# DMB.net
KiCad netlist of a schematic drawn in Altium Designer
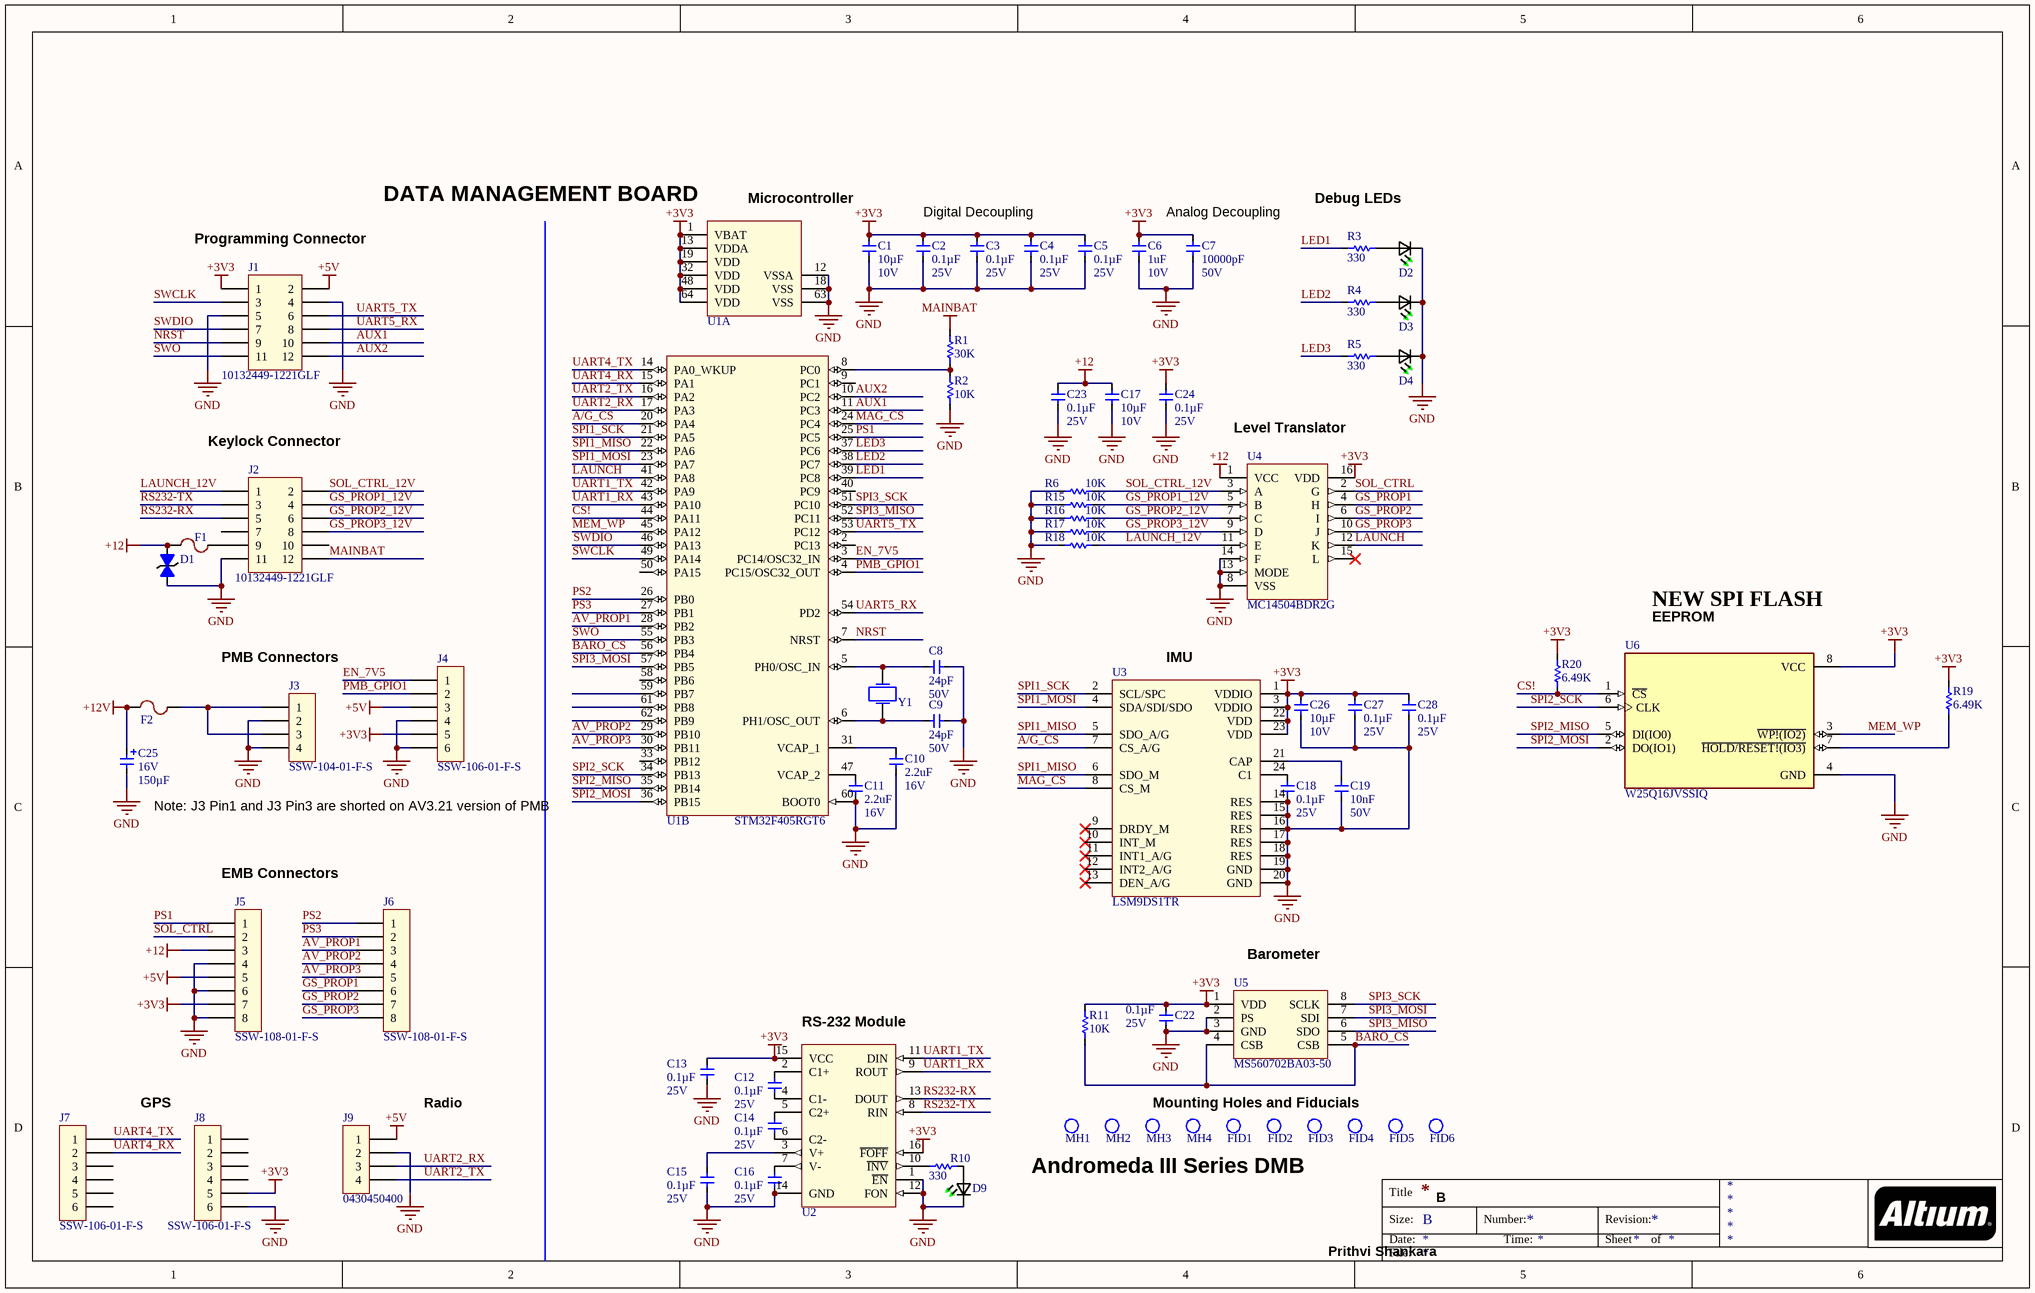
[diagram p0: DMB.SchDoc]

(export (version "E")
  (design (tool "Eeschema 10.0.6"))
  (components
    (comp (ref "C1")
      (value "CL10A106MP8NNNC")
      (footprint "0603[1608]")
      (description "CAP CER 10UF 10V X5R 0603")
      (fields
        (field (name "MANUFACTURER") "Samsung Electro-Mechanics")
        (field (name "TOLERANCE") "±20%")
        (field (name "CAPACITANCE") "10µF")
        (field (name "VOLTAGE - RATED") "10V")
      )
      (libsource (lib "SOARSchematics") (part "CL10A106MP8NNNC"))
    )
    (comp (ref "C2")
      (value "CGA3E2X7R1E104K080AA")
      (footprint "0603[1608]")
      (description "CAP CER 0.1UF 25V X7R 0603")
      (fields
        (field (name "MANUFACTURER") "TDK Corporation")
        (field (name "TOLERANCE") "±10%")
        (field (name "CAPACITANCE") "0.1µF")
        (field (name "VOLTAGE - RATED") "25V")
      )
      (libsource (lib "SOARSchematics") (part "CGA3E2X7R1E104K080AA"))
    )
    (comp (ref "C3")
      (value "CGA3E2X7R1E104K080AA")
      (footprint "0603[1608]")
      (description "CAP CER 0.1UF 25V X7R 0603")
      (fields
        (field (name "MANUFACTURER") "TDK Corporation")
        (field (name "TOLERANCE") "±10%")
        (field (name "CAPACITANCE") "0.1µF")
        (field (name "VOLTAGE - RATED") "25V")
      )
      (libsource (lib "SOARSchematics") (part "CGA3E2X7R1E104K080AA"))
    )
    (comp (ref "C4")
      (value "CGA3E2X7R1E104K080AA")
      (footprint "0603[1608]")
      (description "CAP CER 0.1UF 25V X7R 0603")
      (fields
        (field (name "MANUFACTURER") "TDK Corporation")
        (field (name "TOLERANCE") "±10%")
        (field (name "CAPACITANCE") "0.1µF")
        (field (name "VOLTAGE - RATED") "25V")
      )
      (libsource (lib "SOARSchematics") (part "CGA3E2X7R1E104K080AA"))
    )
    (comp (ref "C5")
      (value "CGA3E2X7R1E104K080AA")
      (footprint "0603[1608]")
      (description "CAP CER 0.1UF 25V X7R 0603")
      (fields
        (field (name "MANUFACTURER") "TDK Corporation")
        (field (name "TOLERANCE") "±10%")
        (field (name "CAPACITANCE") "0.1µF")
        (field (name "VOLTAGE - RATED") "25V")
      )
      (libsource (lib "SOARSchematics") (part "CGA3E2X7R1E104K080AA"))
    )
    (comp (ref "C6")
      (value "CL10A105KP8NNNC")
      (footprint "0603[1608]")
      (description "CAP CER 1UF 10V X5R 0603")
      (fields
        (field (name "MANUFACTURER") "Samsung Electro-Mechanics")
        (field (name "TOLERANCE") "±10%")
        (field (name "CAPACITANCE") "1uF")
        (field (name "VOLTAGE - RATED") "10V")
      )
      (libsource (lib "SOARSchematics") (part "CL10A105KP8NNNC"))
    )
    (comp (ref "C7")
      (value "CGA3E2X7R1H103K080AA")
      (footprint "0603[1608]")
      (description "CAP CER 10000PF 50V X7R 0603")
      (fields
        (field (name "MANUFACTURER") "TDK Corporation")
        (field (name "TOLERANCE") "±10%")
        (field (name "CAPACITANCE") "10000pF")
        (field (name "VOLTAGE - RATED") "50V")
      )
      (libsource (lib "SOARSchematics") (part "CGA3E2X7R1H103K080AA"))
    )
    (comp (ref "C8")
      (value "06035A240JAT2A")
      (footprint "0603[1608]")
      (description "CAP CER 24PF 50V NP0 0603")
      (fields
        (field (name "MANUFACTURER") "AVX Corporation")
        (field (name "TOLERANCE") "±5%")
        (field (name "CAPACITANCE") "24pF")
        (field (name "VOLTAGE - RATED") "50V")
      )
      (libsource (lib "SOARSchematics") (part "06035A240JAT2A"))
    )
    (comp (ref "C9")
      (value "06035A240JAT2A")
      (footprint "0603[1608]")
      (description "CAP CER 24PF 50V NP0 0603")
      (fields
        (field (name "MANUFACTURER") "AVX Corporation")
        (field (name "TOLERANCE") "±5%")
        (field (name "CAPACITANCE") "24pF")
        (field (name "VOLTAGE - RATED") "50V")
      )
      (libsource (lib "SOARSchematics") (part "06035A240JAT2A"))
    )
    (comp (ref "C10")
      (value "C1608X5R1C225K080AB")
      (footprint "0603[1608]")
      (description "CAP CER 2.2UF 16V X5R 0603")
      (fields
        (field (name "MANUFACTURER") "TDK Corporation")
        (field (name "TOLERANCE") "±10%")
        (field (name "CAPACITANCE") "2.2uF")
        (field (name "VOLTAGE - RATED") "16V")
      )
      (libsource (lib "SOARSchematics") (part "C1608X5R1C225K080AB"))
    )
    (comp (ref "C11")
      (value "C1608X5R1C225K080AB")
      (footprint "0603[1608]")
      (description "CAP CER 2.2UF 16V X5R 0603")
      (fields
        (field (name "MANUFACTURER") "TDK Corporation")
        (field (name "TOLERANCE") "±10%")
        (field (name "CAPACITANCE") "2.2uF")
        (field (name "VOLTAGE - RATED") "16V")
      )
      (libsource (lib "SOARSchematics") (part "C1608X5R1C225K080AB"))
    )
    (comp (ref "C12")
      (value "CGA3E2X7R1E104K080AA")
      (footprint "0603[1608]")
      (description "CAP CER 0.1UF 25V X7R 0603")
      (fields
        (field (name "MANUFACTURER") "TDK Corporation")
        (field (name "TOLERANCE") "±10%")
        (field (name "CAPACITANCE") "0.1µF")
        (field (name "VOLTAGE - RATED") "25V")
      )
      (libsource (lib "SOARSchematics") (part "CGA3E2X7R1E104K080AA"))
    )
    (comp (ref "C13")
      (value "CGA3E2X7R1E104K080AA")
      (footprint "0603[1608]")
      (description "CAP CER 0.1UF 25V X7R 0603")
      (fields
        (field (name "MANUFACTURER") "TDK Corporation")
        (field (name "TOLERANCE") "±10%")
        (field (name "CAPACITANCE") "0.1µF")
        (field (name "VOLTAGE - RATED") "25V")
      )
      (libsource (lib "SOARSchematics") (part "CGA3E2X7R1E104K080AA"))
    )
    (comp (ref "C14")
      (value "CGA3E2X7R1E104K080AA")
      (footprint "0603[1608]")
      (description "CAP CER 0.1UF 25V X7R 0603")
      (fields
        (field (name "MANUFACTURER") "TDK Corporation")
        (field (name "TOLERANCE") "±10%")
        (field (name "CAPACITANCE") "0.1µF")
        (field (name "VOLTAGE - RATED") "25V")
      )
      (libsource (lib "SOARSchematics") (part "CGA3E2X7R1E104K080AA"))
    )
    (comp (ref "C15")
      (value "CGA3E2X7R1E104K080AA")
      (footprint "0603[1608]")
      (description "CAP CER 0.1UF 25V X7R 0603")
      (fields
        (field (name "MANUFACTURER") "TDK Corporation")
        (field (name "TOLERANCE") "±10%")
        (field (name "CAPACITANCE") "0.1µF")
        (field (name "VOLTAGE - RATED") "25V")
      )
      (libsource (lib "SOARSchematics") (part "CGA3E2X7R1E104K080AA"))
    )
    (comp (ref "C16")
      (value "CGA3E2X7R1E104K080AA")
      (footprint "0603[1608]")
      (description "CAP CER 0.1UF 25V X7R 0603")
      (fields
        (field (name "MANUFACTURER") "TDK Corporation")
        (field (name "TOLERANCE") "±10%")
        (field (name "CAPACITANCE") "0.1µF")
        (field (name "VOLTAGE - RATED") "25V")
      )
      (libsource (lib "SOARSchematics") (part "CGA3E2X7R1E104K080AA"))
    )
    (comp (ref "C17")
      (value "CL10A106MP8NNNC")
      (footprint "0603[1608]")
      (description "CAP CER 10UF 10V X5R 0603")
      (fields
        (field (name "MANUFACTURER") "Samsung Electro-Mechanics")
        (field (name "TOLERANCE") "±20%")
        (field (name "CAPACITANCE") "10µF")
        (field (name "VOLTAGE - RATED") "10V")
      )
      (libsource (lib "SOARSchematics") (part "CL10A106MP8NNNC"))
    )
    (comp (ref "C18")
      (value "CGA3E2X7R1E104K080AA")
      (footprint "0603[1608]")
      (description "CAP CER 0.1UF 25V X7R 0603")
      (fields
        (field (name "MANUFACTURER") "TDK Corporation")
        (field (name "TOLERANCE") "±10%")
        (field (name "CAPACITANCE") "0.1µF")
        (field (name "VOLTAGE - RATED") "25V")
      )
      (libsource (lib "SOARSchematics") (part "CGA3E2X7R1E104K080AA"))
    )
    (comp (ref "C19")
      (value "GRM1885C1H103JA01D")
      (footprint "0603[1608]")
      (description "CAP CER 10000PF 50V C0G/NP0 0603")
      (fields
        (field (name "MANUFACTURER") "Murata Electronics")
        (field (name "TOLERANCE") "±50%")
        (field (name "CAPACITANCE") "10nF")
        (field (name "VOLTAGE - RATED") "50V")
      )
      (libsource (lib "SOARSchematics") (part "GRM1885C1H103JA01D"))
    )
    (comp (ref "C22")
      (value "CGA3E2X7R1E104K080AA")
      (footprint "0603[1608]")
      (description "CAP CER 0.1UF 25V X7R 0603")
      (fields
        (field (name "MANUFACTURER") "TDK Corporation")
        (field (name "TOLERANCE") "±10%")
        (field (name "CAPACITANCE") "0.1µF")
        (field (name "VOLTAGE - RATED") "25V")
      )
      (libsource (lib "SOARSchematics") (part "CGA3E2X7R1E104K080AA"))
    )
    (comp (ref "C23")
      (value "CGA3E2X7R1E104K080AA")
      (footprint "0603[1608]")
      (description "CAP CER 0.1UF 25V X7R 0603")
      (fields
        (field (name "MANUFACTURER") "TDK Corporation")
        (field (name "TOLERANCE") "±10%")
        (field (name "CAPACITANCE") "0.1µF")
        (field (name "VOLTAGE - RATED") "25V")
      )
      (libsource (lib "SOARSchematics") (part "CGA3E2X7R1E104K080AA"))
    )
    (comp (ref "C24")
      (value "CGA3E2X7R1E104K080AA")
      (footprint "0603[1608]")
      (description "CAP CER 0.1UF 25V X7R 0603")
      (fields
        (field (name "MANUFACTURER") "TDK Corporation")
        (field (name "TOLERANCE") "±10%")
        (field (name "CAPACITANCE") "0.1µF")
        (field (name "VOLTAGE - RATED") "25V")
      )
      (libsource (lib "SOARSchematics") (part "CGA3E2X7R1E104K080AA"))
    )
    (comp (ref "C25")
      (value "TAJD157K016RNJ")
      (footprint "TAJD157K016RNJ")
      (description "CAP TANT 150UF 10% 16V 2917")
      (fields
        (field (name "MANUFACTURER") "AVX Corporation")
        (field (name "TOLERANCE") "±10%")
        (field (name "VOLTAGE - RATED") "16V")
        (field (name "CAPACITANCE") "150µF")
      )
      (libsource (lib "SOARSchematics") (part "TAJD157K016RNJ"))
    )
    (comp (ref "C26")
      (value "CL10A106MP8NNNC")
      (footprint "0603[1608]")
      (description "CAP CER 10UF 10V X5R 0603")
      (fields
        (field (name "MANUFACTURER") "Samsung Electro-Mechanics")
        (field (name "TOLERANCE") "±20%")
        (field (name "CAPACITANCE") "10µF")
        (field (name "VOLTAGE - RATED") "10V")
      )
      (libsource (lib "SOARSchematics") (part "CL10A106MP8NNNC"))
    )
    (comp (ref "C27")
      (value "CGA3E2X7R1E104K080AA")
      (footprint "0603[1608]")
      (description "CAP CER 0.1UF 25V X7R 0603")
      (fields
        (field (name "MANUFACTURER") "TDK Corporation")
        (field (name "TOLERANCE") "±10%")
        (field (name "CAPACITANCE") "0.1µF")
        (field (name "VOLTAGE - RATED") "25V")
      )
      (libsource (lib "SOARSchematics") (part "CGA3E2X7R1E104K080AA"))
    )
    (comp (ref "C28")
      (value "CGA3E2X7R1E104K080AA")
      (footprint "0603[1608]")
      (description "CAP CER 0.1UF 25V X7R 0603")
      (fields
        (field (name "MANUFACTURER") "TDK Corporation")
        (field (name "TOLERANCE") "±10%")
        (field (name "CAPACITANCE") "0.1µF")
        (field (name "VOLTAGE - RATED") "25V")
      )
      (libsource (lib "SOARSchematics") (part "CGA3E2X7R1E104K080AA"))
    )
    (comp (ref "D1")
      (value "CDSOD323-T12C")
      (footprint "CDSOD323-T12C")
      (description "TVS DIODE 12V 28.3V SOD323")
      (fields (field (name "MANUFACTURER") "Bourns Inc."))
      (libsource (lib "SOARSchematics") (part "CDSOD323-T12C"))
    )
    (comp (ref "D2")
      (value "LTST-C191KGKT")
      (footprint "LTST-C191KGKT")
      (description "LED GREEN CLEAR SMD 0603")
      (fields (field (name "MANUFACTURER") "Lite-On Inc."))
      (libsource (lib "SOARSchematics") (part "LTST-C191KGKT"))
    )
    (comp (ref "D3")
      (value "LTST-C191KGKT")
      (footprint "LTST-C191KGKT")
      (description "LED GREEN CLEAR SMD 0603")
      (fields (field (name "MANUFACTURER") "Lite-On Inc."))
      (libsource (lib "SOARSchematics") (part "LTST-C191KGKT"))
    )
    (comp (ref "D4")
      (value "LTST-C191KGKT")
      (footprint "LTST-C191KGKT")
      (description "LED GREEN CLEAR SMD 0603")
      (fields (field (name "MANUFACTURER") "Lite-On Inc."))
      (libsource (lib "SOARSchematics") (part "LTST-C191KGKT"))
    )
    (comp (ref "D9")
      (value "LTST-C191KGKT")
      (footprint "LTST-C191KGKT")
      (description "LED GREEN CLEAR SMD 0603")
      (fields (field (name "MANUFACTURER") "Lite-On Inc."))
      (libsource (lib "SOARSchematics") (part "LTST-C191KGKT"))
    )
    (comp (ref "F1")
      (value "SF-0603FP500M-2")
      (footprint "SF-0603FP500M-2")
      (description "FUSE BOARD MOUNT 5A 32VDC 0603")
      (fields (field (name "MANUFACTURER") "Bourns Inc."))
      (libsource (lib "SOARSchematics") (part "SF-0603FP500M-2"))
    )
    (comp (ref "F2")
      (value "SF-0603FP500M-2")
      (footprint "SF-0603FP500M-2")
      (description "FUSE BOARD MOUNT 5A 32VDC 0603")
      (fields (field (name "MANUFACTURER") "Bourns Inc."))
      (libsource (lib "SOARSchematics") (part "SF-0603FP500M-2"))
    )
    (comp (ref "FID1")
      (value "FID_1MM_ROUND_SL")
      (footprint "FID_1MM_ROUND_SL")
      (description "Fiducial 1mm Round Single Layer")
      (libsource (lib "SOARSchematics") (part "FID_1MM_ROUND_SL"))
    )
    (comp (ref "FID2")
      (value "FID_1MM_ROUND_SL")
      (footprint "FID_1MM_ROUND_SL")
      (description "Fiducial 1mm Round Single Layer")
      (libsource (lib "SOARSchematics") (part "FID_1MM_ROUND_SL"))
    )
    (comp (ref "FID3")
      (value "FID_1MM_ROUND_SL")
      (footprint "FID_1MM_ROUND_SL")
      (description "Fiducial 1mm Round Single Layer")
      (libsource (lib "SOARSchematics") (part "FID_1MM_ROUND_SL"))
    )
    (comp (ref "FID4")
      (value "FID_1MM_ROUND_SL")
      (footprint "FID_1MM_ROUND_SL")
      (description "Fiducial 1mm Round Single Layer")
      (libsource (lib "SOARSchematics") (part "FID_1MM_ROUND_SL"))
    )
    (comp (ref "FID5")
      (value "FID_1MM_ROUND_SL")
      (footprint "FID_1MM_ROUND_SL")
      (description "Fiducial 1mm Round Single Layer")
      (libsource (lib "SOARSchematics") (part "FID_1MM_ROUND_SL"))
    )
    (comp (ref "FID6")
      (value "FID_1MM_ROUND_SL")
      (footprint "FID_1MM_ROUND_SL")
      (description "Fiducial 1mm Round Single Layer")
      (libsource (lib "SOARSchematics") (part "FID_1MM_ROUND_SL"))
    )
    (comp (ref "J1")
      (value "10132449-1221GLF")
      (footprint "10132449-1221GLF")
      (description "CONN HEADER R/A 12POS 3MM")
      (fields (field (name "MANUFACTURER") "Amphenol ICC (FCI)"))
      (libsource (lib "SOARSchematics") (part "10132449-1221GLF"))
    )
    (comp (ref "J2")
      (value "10132449-1221GLF")
      (footprint "10132449-1221GLF")
      (description "CONN HEADER R/A 12POS 3MM")
      (fields (field (name "MANUFACTURER") "Amphenol ICC (FCI)"))
      (libsource (lib "SOARSchematics") (part "10132449-1221GLF"))
    )
    (comp (ref "J3")
      (value "SSW-104-01-F-S")
      (footprint "SSW-104-01-F-S")
      (description "CONN RCPT 4POS FEMALE 0.1 GOLD PCB")
      (fields (field (name "MANUFACTURER") "Samtec Inc."))
      (libsource (lib "SOARSchematics") (part "SSW-104-01-F-S"))
    )
    (comp (ref "J4")
      (value "SSW-106-01-F-S")
      (footprint "SSW-106-01-F-S")
      (description "CONN RCPT 6POS FEMALE 0.1 GOLD PCB")
      (fields (field (name "MANUFACTURER") "Samtec Inc."))
      (libsource (lib "") (part "SSW-106-01-F-S_1"))
    )
    (comp (ref "J5")
      (value "SSW-108-01-F-S")
      (footprint "SSW-108-01-F-S")
      (description "CONN RCPT 8POS FEMALE 0.1 GOLD PCB")
      (fields (field (name "MANUFACTURER") "Samtec Inc."))
      (libsource (lib "SOARSchematics") (part "SSW-108-01-F-S"))
    )
    (comp (ref "J6")
      (value "SSW-108-01-F-S")
      (footprint "SSW-108-01-F-S")
      (description "CONN RCPT 8POS FEMALE 0.1 GOLD PCB")
      (fields (field (name "MANUFACTURER") "Samtec Inc."))
      (libsource (lib "SOARSchematics") (part "SSW-108-01-F-S"))
    )
    (comp (ref "J7")
      (value "SSW-106-01-F-S")
      (footprint "SSW-106-01-F-S")
      (description "CONN RCPT 6POS FEMALE 0.1 GOLD PCB")
      (fields (field (name "MANUFACTURER") "Samtec Inc."))
      (libsource (lib "SOARSchematics") (part "SSW-106-01-F-S"))
    )
    (comp (ref "J8")
      (value "SSW-106-01-F-S")
      (footprint "SSW-106-01-F-S")
      (description "CONN RCPT 6POS FEMALE 0.1 GOLD PCB")
      (fields (field (name "MANUFACTURER") "Samtec Inc."))
      (libsource (lib "SOARSchematics") (part "SSW-106-01-F-S"))
    )
    (comp (ref "J9")
      (value "0430450400")
      (footprint "0430450400")
      (description "CONN HEADER R/A 4POS 3MM")
      (fields (field (name "MANUFACTURER") "Molex"))
      (libsource (lib "SOARSchematics") (part "0430450400"))
    )
    (comp (ref "MH1")
      (value "Mounting Hole")
      (footprint "MOUNT-HOLE")
      (description "#4 Screw, 0.116in Diameter")
      (libsource (lib "SOARSchematics") (part "Mounting Hole"))
    )
    (comp (ref "MH2")
      (value "Mounting Hole")
      (footprint "MOUNT-HOLE")
      (description "#4 Screw, 0.116in Diameter")
      (libsource (lib "SOARSchematics") (part "Mounting Hole"))
    )
    (comp (ref "MH3")
      (value "Mounting Hole")
      (footprint "MOUNT-HOLE")
      (description "#4 Screw, 0.116in Diameter")
      (libsource (lib "SOARSchematics") (part "Mounting Hole"))
    )
    (comp (ref "MH4")
      (value "Mounting Hole")
      (footprint "MOUNT-HOLE")
      (description "#4 Screw, 0.116in Diameter")
      (libsource (lib "SOARSchematics") (part "Mounting Hole"))
    )
    (comp (ref "R1")
      (value "RC0603FR-0730KL")
      (footprint "0603[1608]")
      (description "RES SMD 30K OHM 1% 1/10W 0603")
      (fields
        (field (name "TOLERANCE") "±1%")
        (field (name "MANUFACTURER") "Yageo")
        (field (name "RESISTANCE") "30K")
      )
      (libsource (lib "SOARSchematics") (part "RC0603FR-0730KL"))
    )
    (comp (ref "R2")
      (value "ERJ-3GEYJ103V")
      (footprint "0603[1608]")
      (description "RES SMD 10K OHM 5% 1/10W 0603")
      (fields
        (field (name "TOLERANCE") "±5%")
        (field (name "MANUFACTURER") "Panasonic Electronic Components")
        (field (name "RESISTANCE") "10K")
      )
      (libsource (lib "SOARSchematics") (part "ERJ-3GEYJ103V"))
    )
    (comp (ref "R3")
      (value "RC1608F331CS")
      (footprint "0603[1608]")
      (description "RES SMD 330 OHM 1% 1/10W 0603")
      (fields
        (field (name "TOLERANCE") "±1%")
        (field (name "MANUFACTURER") "Samsung Electro-Mechanics")
        (field (name "RESISTANCE") "330")
      )
      (libsource (lib "SOARSchematics") (part "RC1608F331CS"))
    )
    (comp (ref "R4")
      (value "RC1608F331CS")
      (footprint "0603[1608]")
      (description "RES SMD 330 OHM 1% 1/10W 0603")
      (fields
        (field (name "TOLERANCE") "±1%")
        (field (name "MANUFACTURER") "Samsung Electro-Mechanics")
        (field (name "RESISTANCE") "330")
      )
      (libsource (lib "SOARSchematics") (part "RC1608F331CS"))
    )
    (comp (ref "R5")
      (value "RC1608F331CS")
      (footprint "0603[1608]")
      (description "RES SMD 330 OHM 1% 1/10W 0603")
      (fields
        (field (name "TOLERANCE") "±1%")
        (field (name "MANUFACTURER") "Samsung Electro-Mechanics")
        (field (name "RESISTANCE") "330")
      )
      (libsource (lib "SOARSchematics") (part "RC1608F331CS"))
    )
    (comp (ref "R6")
      (value "ERJ-3GEYJ103V")
      (footprint "0603[1608]")
      (description "RES SMD 10K OHM 5% 1/10W 0603")
      (fields
        (field (name "TOLERANCE") "±5%")
        (field (name "MANUFACTURER") "Panasonic Electronic Components")
        (field (name "RESISTANCE") "10K")
      )
      (libsource (lib "SOARSchematics") (part "ERJ-3GEYJ103V"))
    )
    (comp (ref "R10")
      (value "RC1608F331CS")
      (footprint "0603[1608]")
      (description "RES SMD 330 OHM 1% 1/10W 0603")
      (fields
        (field (name "TOLERANCE") "±1%")
        (field (name "MANUFACTURER") "Samsung Electro-Mechanics")
        (field (name "RESISTANCE") "330")
      )
      (libsource (lib "SOARSchematics") (part "RC1608F331CS"))
    )
    (comp (ref "R11")
      (value "ERJ-3GEYJ103V")
      (footprint "0603[1608]")
      (description "RES SMD 10K OHM 5% 1/10W 0603")
      (fields
        (field (name "TOLERANCE") "±5%")
        (field (name "MANUFACTURER") "Panasonic Electronic Components")
        (field (name "RESISTANCE") "10K")
      )
      (libsource (lib "SOARSchematics") (part "ERJ-3GEYJ103V"))
    )
    (comp (ref "R15")
      (value "ERJ-3GEYJ103V")
      (footprint "0603[1608]")
      (description "RES SMD 10K OHM 5% 1/10W 0603")
      (fields
        (field (name "TOLERANCE") "±5%")
        (field (name "MANUFACTURER") "Panasonic Electronic Components")
        (field (name "RESISTANCE") "10K")
      )
      (libsource (lib "SOARSchematics") (part "ERJ-3GEYJ103V"))
    )
    (comp (ref "R16")
      (value "ERJ-3GEYJ103V")
      (footprint "0603[1608]")
      (description "RES SMD 10K OHM 5% 1/10W 0603")
      (fields
        (field (name "TOLERANCE") "±5%")
        (field (name "MANUFACTURER") "Panasonic Electronic Components")
        (field (name "RESISTANCE") "10K")
      )
      (libsource (lib "SOARSchematics") (part "ERJ-3GEYJ103V"))
    )
    (comp (ref "R17")
      (value "ERJ-3GEYJ103V")
      (footprint "0603[1608]")
      (description "RES SMD 10K OHM 5% 1/10W 0603")
      (fields
        (field (name "TOLERANCE") "±5%")
        (field (name "MANUFACTURER") "Panasonic Electronic Components")
        (field (name "RESISTANCE") "10K")
      )
      (libsource (lib "SOARSchematics") (part "ERJ-3GEYJ103V"))
    )
    (comp (ref "R18")
      (value "ERJ-3GEYJ103V")
      (footprint "0603[1608]")
      (description "RES SMD 10K OHM 5% 1/10W 0603")
      (fields
        (field (name "TOLERANCE") "±5%")
        (field (name "MANUFACTURER") "Panasonic Electronic Components")
        (field (name "RESISTANCE") "10K")
      )
      (libsource (lib "SOARSchematics") (part "ERJ-3GEYJ103V"))
    )
    (comp (ref "R19")
      (value "RT0603DRE076K49L")
      (footprint "0603[1608]")
      (description "RES SMD 6.49KOHM 0.5% 1/10W 0603")
      (fields
        (field (name "TOLERANCE") "±0.5%")
        (field (name "MANUFACTURER") "Yageo")
        (field (name "RESISTANCE") "6.49K")
      )
      (libsource (lib "SOARSchematics") (part "RT0603DRE076K49L"))
    )
    (comp (ref "R20")
      (value "RT0603DRE076K49L")
      (footprint "0603[1608]")
      (description "RES SMD 6.49KOHM 0.5% 1/10W 0603")
      (fields
        (field (name "TOLERANCE") "±0.5%")
        (field (name "MANUFACTURER") "Yageo")
        (field (name "RESISTANCE") "6.49K")
      )
      (libsource (lib "SOARSchematics") (part "RT0603DRE076K49L"))
    )
    (comp (ref "U1")
      (value "STM32F405RGT6")
      (footprint "TSQFP50P1200X1200X160-64N")
      (description "IC MCU 32BIT 1MB FLASH 64LQFP")
      (fields (field (name "MANUFACTURER") "STMicroelectronics"))
      (libsource (lib "SOARSchematics") (part "STM32F405RGT6"))
    )
    (comp (ref "U2")
      (value "MAX3221ECPWR")
      (footprint "SOP65P780X200-16N")
      (description "IC TRANSCEIVER FULL 1/1 16TSSOP")
      (fields (field (name "MANUFACTURER") "Texas Instruments") (field (name "BASE PART NUMBER") "MAX3221E"))
      (libsource (lib "SOARSchematics") (part "MAX3221ECPWR"))
    )
    (comp (ref "U3")
      (value "LSM9DS1TR")
      (footprint "LSM9DS1TR")
      (description "IMU ACCEL/GYRO/MAG I2C/SPI 24LGA")
      (fields (field (name "MANUFACTURER") "STMicroelectronics"))
      (libsource (lib "SOARSchematics") (part "LSM9DS1TR"))
    )
    (comp (ref "U4")
      (value "MC14504BDR2G")
      (footprint "MC14504BDR2G")
      (description "IC TRNSLTR UNIDIRECTIONAL 16SOIC")
      (fields (field (name "MANUFACTURER") "ON Semiconductor"))
      (libsource (lib "SOARSchematics") (part "MC14504BDR2G"))
    )
    (comp (ref "U5")
      (value "MS560702BA03-50")
      (footprint "MS560702BA03-50")
      (description "BAROMETRIC PRESSURE SENSOR")
      (fields
        (field (name "DIGI-KEY PART NUMBER") "223-1198-1-ND")
        (field (name "MANUFACTURER") "TE Connectivity Measurement Specialties")
      )
      (libsource (lib "SOARSchematics") (part "MS560702BA03-50"))
    )
    (comp (ref "U6")
      (value "W25Q16JVSSIQ")
      (footprint "W25Q16JVSSIQ")
      (description "FLASH - NOR Memory IC 16Mb _2M x 8_ SPI - Quad I/O 133MHz 8-SOIC")
      (fields (field (name "MF") "Winbond Electronics"))
      (libsource (lib "SOARSchematics") (part "W25Q16JVSSIQ"))
    )
    (comp (ref "Y1")
      (value "ABLS-8.000MHZ-B2-T")
      (footprint "ABLS-8.000MHZ-B2-T")
      (description "CRYSTAL 8.0000MHZ 18PF SMD")
      (fields (field (name "MANUFACTURER") "Abracon LLC"))
      (libsource (lib "SOARSchematics") (part "ABLS-8.000MHZ-B2-T"))
    )
  )
  (nets
    (net (code "1") (name "+3V3") (class "Default")
      (node (ref "C1") (pin "2") (pinfunction "2_2") (pintype "passive"))
      (node (ref "C13") (pin "2") (pinfunction "2_2") (pintype "passive"))
      (node (ref "C2") (pin "2") (pinfunction "2_2") (pintype "passive"))
      (node (ref "C22") (pin "2") (pinfunction "2_2") (pintype "passive"))
      (node (ref "C24") (pin "2") (pinfunction "2_2") (pintype "passive"))
      (node (ref "C26") (pin "2") (pinfunction "2_2") (pintype "passive"))
      (node (ref "C27") (pin "2") (pinfunction "2_2") (pintype "passive"))
      (node (ref "C28") (pin "2") (pinfunction "2_2") (pintype "passive"))
      (node (ref "C3") (pin "2") (pinfunction "2_2") (pintype "passive"))
      (node (ref "C4") (pin "2") (pinfunction "2_2") (pintype "passive"))
      (node (ref "C5") (pin "2") (pinfunction "2_2") (pintype "passive"))
      (node (ref "C6") (pin "2") (pinfunction "2_2") (pintype "passive"))
      (node (ref "C7") (pin "2") (pinfunction "2_2") (pintype "passive"))
      (node (ref "J1") (pin "1") (pinfunction "1_1") (pintype "passive"))
      (node (ref "J4") (pin "5") (pinfunction "5_5") (pintype "passive"))
      (node (ref "J5") (pin "7") (pinfunction "7_7") (pintype "passive"))
      (node (ref "J8") (pin "5") (pinfunction "5_5") (pintype "passive"))
      (node (ref "R11") (pin "2") (pinfunction "2_2") (pintype "passive"))
      (node (ref "R19") (pin "2") (pinfunction "2_2") (pintype "passive"))
      (node (ref "R20") (pin "2") (pinfunction "2_2") (pintype "passive"))
      (node (ref "U1") (pin "1") (pinfunction "VBAT_1") (pintype "power_in"))
      (node (ref "U1") (pin "13") (pinfunction "VDDA_13") (pintype "power_in"))
      (node (ref "U1") (pin "19") (pinfunction "VDD_19") (pintype "power_in"))
      (node (ref "U1") (pin "32") (pinfunction "VDD_32") (pintype "power_in"))
      (node (ref "U1") (pin "48") (pinfunction "VDD_48") (pintype "power_in"))
      (node (ref "U1") (pin "64") (pinfunction "VDD_64") (pintype "power_in"))
      (node (ref "U2") (pin "15") (pinfunction "VCC_15") (pintype "passive"))
      (node (ref "U2") (pin "16") (pinfunction "~{FOFF}_16") (pintype "input"))
      (node (ref "U3") (pin "1") (pinfunction "VDDIO_1") (pintype "power_in"))
      (node (ref "U3") (pin "22") (pinfunction "VDD_22") (pintype "power_in"))
      (node (ref "U3") (pin "23") (pinfunction "VDD_23") (pintype "power_in"))
      (node (ref "U3") (pin "3") (pinfunction "VDDIO_3") (pintype "power_in"))
      (node (ref "U4") (pin "16") (pinfunction "VDD_16") (pintype "power_in"))
      (node (ref "U5") (pin "1") (pinfunction "VDD_1") (pintype "power_in"))
      (node (ref "U6") (pin "8") (pinfunction "VCC_8") (pintype "power_in"))
    )
    (net (code "2") (name "+5V") (class "Default")
      (node (ref "J1") (pin "2") (pinfunction "2_2") (pintype "passive"))
      (node (ref "J4") (pin "3") (pinfunction "3_3") (pintype "passive"))
      (node (ref "J5") (pin "5") (pinfunction "5_5") (pintype "passive"))
      (node (ref "J9") (pin "1") (pinfunction "1_1") (pintype "passive"))
    )
    (net (code "3") (name "+12") (class "Default")
      (node (ref "C17") (pin "2") (pinfunction "2_2") (pintype "passive"))
      (node (ref "C23") (pin "2") (pinfunction "2_2") (pintype "passive"))
      (node (ref "D1") (pin "1") (pinfunction "1_1") (pintype "power_in"))
      (node (ref "F1") (pin "1") (pinfunction "1_1") (pintype "passive"))
      (node (ref "J5") (pin "3") (pinfunction "3_3") (pintype "passive"))
      (node (ref "U4") (pin "1") (pinfunction "VCC_1") (pintype "power_in"))
    )
    (net (code "4") (name "+12V") (class "Default")
      (node (ref "C25") (pin "1") (pinfunction "1_1") (pintype "passive"))
      (node (ref "F2") (pin "1") (pinfunction "1_1") (pintype "passive"))
    )
    (net (code "6") (name "/AUX1") (class "Default")
      (node (ref "J1") (pin "10") (pinfunction "10_10") (pintype "passive"))
      (node (ref "U1") (pin "11") (pinfunction "PC3_11") (pintype "bidirectional"))
    )
    (net (code "7") (name "/AUX2") (class "Default")
      (node (ref "J1") (pin "12") (pinfunction "12_12") (pintype "passive"))
      (node (ref "U1") (pin "10") (pinfunction "PC2_10") (pintype "bidirectional"))
    )
    (net (code "8") (name "/AV_PROP1") (class "Default")
      (node (ref "J6") (pin "3") (pinfunction "3_3") (pintype "passive"))
      (node (ref "U1") (pin "28") (pinfunction "PB2_28") (pintype "bidirectional"))
    )
    (net (code "9") (name "/AV_PROP2") (class "Default")
      (node (ref "J6") (pin "4") (pinfunction "4_4") (pintype "passive"))
      (node (ref "U1") (pin "29") (pinfunction "PB10_29") (pintype "bidirectional"))
    )
    (net (code "10") (name "/AV_PROP3") (class "Default")
      (node (ref "J6") (pin "5") (pinfunction "5_5") (pintype "passive"))
      (node (ref "U1") (pin "30") (pinfunction "PB11_30") (pintype "bidirectional"))
    )
    (net (code "11") (name "/A{slash}G_~{CS}") (class "Default")
      (node (ref "U1") (pin "20") (pinfunction "PA4_20") (pintype "bidirectional"))
      (node (ref "U3") (pin "7") (pinfunction "CS_A/G_7") (pintype "passive"))
    )
    (net (code "12") (name "/BARO_~{CS}") (class "Default")
      (node (ref "R11") (pin "1") (pinfunction "1_1") (pintype "passive"))
      (node (ref "U1") (pin "56") (pinfunction "PB4_56") (pintype "bidirectional"))
      (node (ref "U5") (pin "4") (pinfunction "CSB_4") (pintype "passive"))
      (node (ref "U5") (pin "5") (pinfunction "CSB_5") (pintype "passive"))
    )
    (net (code "13") (name "/CS!") (class "Default")
      (node (ref "R20") (pin "1") (pinfunction "1_1") (pintype "passive"))
      (node (ref "U1") (pin "44") (pinfunction "PA11_44") (pintype "bidirectional"))
      (node (ref "U6") (pin "1") (pinfunction "~{CS}_1") (pintype "input"))
    )
    (net (code "14") (name "/EN_7V5") (class "Default")
      (node (ref "J4") (pin "1") (pinfunction "1_1") (pintype "passive"))
      (node (ref "U1") (pin "3") (pinfunction "PC14/OSC32_IN_3") (pintype "bidirectional"))
    )
    (net (code "15") (name "/GS_PROP1") (class "Default")
      (node (ref "J6") (pin "6") (pinfunction "6_6") (pintype "passive"))
      (node (ref "U4") (pin "4") (pinfunction "H_4") (pintype "output"))
    )
    (net (code "16") (name "/GS_PROP1_12V") (class "Default")
      (node (ref "J2") (pin "4") (pinfunction "4_4") (pintype "passive"))
      (node (ref "R15") (pin "2") (pinfunction "2_2") (pintype "passive"))
      (node (ref "U4") (pin "5") (pinfunction "B_5") (pintype "input"))
    )
    (net (code "17") (name "/GS_PROP2") (class "Default")
      (node (ref "J6") (pin "7") (pinfunction "7_7") (pintype "passive"))
      (node (ref "U4") (pin "6") (pinfunction "I_6") (pintype "output"))
    )
    (net (code "18") (name "/GS_PROP2_12V") (class "Default")
      (node (ref "J2") (pin "6") (pinfunction "6_6") (pintype "passive"))
      (node (ref "R16") (pin "2") (pinfunction "2_2") (pintype "passive"))
      (node (ref "U4") (pin "7") (pinfunction "C_7") (pintype "input"))
    )
    (net (code "19") (name "/GS_PROP3") (class "Default")
      (node (ref "J6") (pin "8") (pinfunction "8_8") (pintype "passive"))
      (node (ref "U4") (pin "10") (pinfunction "J_10") (pintype "output"))
    )
    (net (code "20") (name "/GS_PROP3_12V") (class "Default")
      (node (ref "J2") (pin "8") (pinfunction "8_8") (pintype "passive"))
      (node (ref "R17") (pin "2") (pinfunction "2_2") (pintype "passive"))
      (node (ref "U4") (pin "9") (pinfunction "D_9") (pintype "input"))
    )
    (net (code "21") (name "/LAUNCH") (class "Default")
      (node (ref "U1") (pin "41") (pinfunction "PA8_41") (pintype "bidirectional"))
      (node (ref "U4") (pin "12") (pinfunction "K_12") (pintype "output"))
    )
    (net (code "22") (name "/LAUNCH_12V") (class "Default")
      (node (ref "J2") (pin "1") (pinfunction "1_1") (pintype "passive"))
      (node (ref "R18") (pin "2") (pinfunction "2_2") (pintype "passive"))
      (node (ref "U4") (pin "11") (pinfunction "E_11") (pintype "input"))
    )
    (net (code "23") (name "/LED1") (class "Default")
      (node (ref "R3") (pin "2") (pinfunction "2_2") (pintype "passive"))
      (node (ref "U1") (pin "39") (pinfunction "PC8_39") (pintype "bidirectional"))
    )
    (net (code "24") (name "/LED2") (class "Default")
      (node (ref "R4") (pin "2") (pinfunction "2_2") (pintype "passive"))
      (node (ref "U1") (pin "38") (pinfunction "PC7_38") (pintype "bidirectional"))
    )
    (net (code "25") (name "/LED3") (class "Default")
      (node (ref "R5") (pin "2") (pinfunction "2_2") (pintype "passive"))
      (node (ref "U1") (pin "37") (pinfunction "PC6_37") (pintype "bidirectional"))
    )
    (net (code "26") (name "/MAG_~{CS}") (class "Default")
      (node (ref "U1") (pin "24") (pinfunction "PC4_24") (pintype "bidirectional"))
      (node (ref "U3") (pin "8") (pinfunction "CS_M_8") (pintype "passive"))
    )
    (net (code "27") (name "/MEM_WP") (class "Default")
      (node (ref "U1") (pin "45") (pinfunction "PA12_45") (pintype "bidirectional"))
      (node (ref "U6") (pin "3") (pinfunction "~{WP!(IO2)}_3") (pintype "bidirectional"))
    )
    (net (code "28") (name "/NRST") (class "Default")
      (node (ref "J1") (pin "9") (pinfunction "9_9") (pintype "passive"))
      (node (ref "U1") (pin "7") (pinfunction "NRST_7") (pintype "bidirectional"))
    )
    (net (code "29") (name "/PMB_GPIO1") (class "Default")
      (node (ref "J4") (pin "2") (pinfunction "2_2") (pintype "passive"))
      (node (ref "U1") (pin "4") (pinfunction "PC15/OSC32_OUT_4") (pintype "bidirectional"))
    )
    (net (code "30") (name "/PS1") (class "Default")
      (node (ref "J5") (pin "1") (pinfunction "1_1") (pintype "passive"))
      (node (ref "U1") (pin "25") (pinfunction "PC5_25") (pintype "bidirectional"))
    )
    (net (code "31") (name "/PS2") (class "Default")
      (node (ref "J6") (pin "1") (pinfunction "1_1") (pintype "passive"))
      (node (ref "U1") (pin "26") (pinfunction "PB0_26") (pintype "bidirectional"))
    )
    (net (code "32") (name "/PS3") (class "Default")
      (node (ref "J6") (pin "2") (pinfunction "2_2") (pintype "passive"))
      (node (ref "U1") (pin "27") (pinfunction "PB1_27") (pintype "bidirectional"))
    )
    (net (code "33") (name "/RS232-RX") (class "Default")
      (node (ref "J2") (pin "5") (pinfunction "5_5") (pintype "passive"))
      (node (ref "U2") (pin "13") (pinfunction "DOUT_13") (pintype "output"))
    )
    (net (code "34") (name "/RS232-TX") (class "Default")
      (node (ref "J2") (pin "3") (pinfunction "3_3") (pintype "passive"))
      (node (ref "U2") (pin "8") (pinfunction "RIN_8") (pintype "input"))
    )
    (net (code "35") (name "/SOL_CTRL") (class "Default")
      (node (ref "J5") (pin "2") (pinfunction "2_2") (pintype "passive"))
      (node (ref "U4") (pin "2") (pinfunction "G_2") (pintype "output"))
    )
    (net (code "36") (name "/SOL_CTRL_12V") (class "Default")
      (node (ref "J2") (pin "2") (pinfunction "2_2") (pintype "passive"))
      (node (ref "R6") (pin "2") (pinfunction "2_2") (pintype "passive"))
      (node (ref "U4") (pin "3") (pinfunction "A_3") (pintype "input"))
    )
    (net (code "37") (name "/SPI1_MISO") (class "Default")
      (node (ref "U1") (pin "22") (pinfunction "PA6_22") (pintype "bidirectional"))
      (node (ref "U3") (pin "5") (pinfunction "SDO_A/G_5") (pintype "passive"))
      (node (ref "U3") (pin "6") (pinfunction "SDO_M_6") (pintype "passive"))
    )
    (net (code "38") (name "/SPI1_MOSI") (class "Default")
      (node (ref "U1") (pin "23") (pinfunction "PA7_23") (pintype "bidirectional"))
      (node (ref "U3") (pin "4") (pinfunction "SDA/SDI/SDO_4") (pintype "passive"))
    )
    (net (code "39") (name "/SPI1_SCK") (class "Default")
      (node (ref "U1") (pin "21") (pinfunction "PA5_21") (pintype "bidirectional"))
      (node (ref "U3") (pin "2") (pinfunction "SCL/SPC_2") (pintype "passive"))
    )
    (net (code "40") (name "/SPI2_MISO") (class "Default")
      (node (ref "U1") (pin "35") (pinfunction "PB14_35") (pintype "bidirectional"))
      (node (ref "U6") (pin "5") (pinfunction "DI(IO0)_5") (pintype "bidirectional"))
    )
    (net (code "41") (name "/SPI2_MOSI") (class "Default")
      (node (ref "U1") (pin "36") (pinfunction "PB15_36") (pintype "bidirectional"))
      (node (ref "U6") (pin "2") (pinfunction "DO(IO1)_2") (pintype "bidirectional"))
    )
    (net (code "42") (name "/SPI2_SCK") (class "Default")
      (node (ref "U1") (pin "34") (pinfunction "PB13_34") (pintype "bidirectional"))
      (node (ref "U6") (pin "6") (pinfunction "CLK_6") (pintype "input"))
    )
    (net (code "43") (name "/SPI3_MISO") (class "Default")
      (node (ref "U1") (pin "52") (pinfunction "PC11_52") (pintype "bidirectional"))
      (node (ref "U5") (pin "6") (pinfunction "SDO_6") (pintype "passive"))
    )
    (net (code "44") (name "/SPI3_MOSI") (class "Default")
      (node (ref "U1") (pin "57") (pinfunction "PB5_57") (pintype "bidirectional"))
      (node (ref "U5") (pin "7") (pinfunction "SDI_7") (pintype "passive"))
    )
    (net (code "45") (name "/SPI3_SCK") (class "Default")
      (node (ref "U1") (pin "51") (pinfunction "PC10_51") (pintype "bidirectional"))
      (node (ref "U5") (pin "8") (pinfunction "SCLK_8") (pintype "passive"))
    )
    (net (code "46") (name "/SWCLK") (class "Default")
      (node (ref "J1") (pin "3") (pinfunction "3_3") (pintype "passive"))
      (node (ref "U1") (pin "49") (pinfunction "PA14_49") (pintype "bidirectional"))
    )
    (net (code "47") (name "/SWDIO") (class "Default")
      (node (ref "J1") (pin "7") (pinfunction "7_7") (pintype "passive"))
      (node (ref "U1") (pin "46") (pinfunction "PA13_46") (pintype "bidirectional"))
    )
    (net (code "48") (name "/SWO") (class "Default")
      (node (ref "J1") (pin "11") (pinfunction "11_11") (pintype "passive"))
      (node (ref "U1") (pin "55") (pinfunction "PB3_55") (pintype "bidirectional"))
    )
    (net (code "49") (name "/UART1_RX") (class "Default")
      (node (ref "U1") (pin "43") (pinfunction "PA10_43") (pintype "bidirectional"))
      (node (ref "U2") (pin "9") (pinfunction "ROUT_9") (pintype "output"))
    )
    (net (code "50") (name "/UART1_TX") (class "Default")
      (node (ref "U1") (pin "42") (pinfunction "PA9_42") (pintype "bidirectional"))
      (node (ref "U2") (pin "11") (pinfunction "DIN_11") (pintype "input"))
    )
    (net (code "51") (name "/UART2_RX") (class "Default")
      (node (ref "J9") (pin "3") (pinfunction "3_3") (pintype "passive"))
      (node (ref "U1") (pin "17") (pinfunction "PA3_17") (pintype "bidirectional"))
    )
    (net (code "52") (name "/UART2_TX") (class "Default")
      (node (ref "J9") (pin "4") (pinfunction "4_4") (pintype "passive"))
      (node (ref "U1") (pin "16") (pinfunction "PA2_16") (pintype "bidirectional"))
    )
    (net (code "53") (name "/UART4_RX") (class "Default")
      (node (ref "J7") (pin "2") (pinfunction "2_2") (pintype "passive"))
      (node (ref "U1") (pin "15") (pinfunction "PA1_15") (pintype "bidirectional"))
    )
    (net (code "54") (name "/UART4_TX") (class "Default")
      (node (ref "J7") (pin "1") (pinfunction "1_1") (pintype "passive"))
      (node (ref "U1") (pin "14") (pinfunction "PA0_WKUP_14") (pintype "bidirectional"))
    )
    (net (code "55") (name "/UART5_RX") (class "Default")
      (node (ref "J1") (pin "8") (pinfunction "8_8") (pintype "passive"))
      (node (ref "U1") (pin "54") (pinfunction "PD2_54") (pintype "bidirectional"))
    )
    (net (code "56") (name "/UART5_TX") (class "Default")
      (node (ref "J1") (pin "6") (pinfunction "6_6") (pintype "passive"))
      (node (ref "U1") (pin "53") (pinfunction "PC12_53") (pintype "bidirectional"))
    )
    (net (code "57") (name "GND") (class "Default")
      (node (ref "C1") (pin "1") (pinfunction "1_1") (pintype "passive"))
      (node (ref "C10") (pin "1") (pinfunction "1_1") (pintype "passive"))
      (node (ref "C11") (pin "1") (pinfunction "1_1") (pintype "passive"))
      (node (ref "C13") (pin "1") (pinfunction "1_1") (pintype "passive"))
      (node (ref "C15") (pin "1") (pinfunction "1_1") (pintype "passive"))
      (node (ref "C16") (pin "1") (pinfunction "1_1") (pintype "passive"))
      (node (ref "C17") (pin "1") (pinfunction "1_1") (pintype "passive"))
      (node (ref "C18") (pin "1") (pinfunction "1_1") (pintype "passive"))
      (node (ref "C19") (pin "1") (pinfunction "1_1") (pintype "passive"))
      (node (ref "C2") (pin "1") (pinfunction "1_1") (pintype "passive"))
      (node (ref "C22") (pin "1") (pinfunction "1_1") (pintype "passive"))
      (node (ref "C23") (pin "1") (pinfunction "1_1") (pintype "passive"))
      (node (ref "C24") (pin "1") (pinfunction "1_1") (pintype "passive"))
      (node (ref "C25") (pin "2") (pinfunction "2_2") (pintype "passive"))
      (node (ref "C26") (pin "1") (pinfunction "1_1") (pintype "passive"))
      (node (ref "C27") (pin "1") (pinfunction "1_1") (pintype "passive"))
      (node (ref "C28") (pin "1") (pinfunction "1_1") (pintype "passive"))
      (node (ref "C3") (pin "1") (pinfunction "1_1") (pintype "passive"))
      (node (ref "C4") (pin "1") (pinfunction "1_1") (pintype "passive"))
      (node (ref "C5") (pin "1") (pinfunction "1_1") (pintype "passive"))
      (node (ref "C6") (pin "1") (pinfunction "1_1") (pintype "passive"))
      (node (ref "C7") (pin "1") (pinfunction "1_1") (pintype "passive"))
      (node (ref "C8") (pin "2") (pinfunction "2_2") (pintype "passive"))
      (node (ref "C9") (pin "2") (pinfunction "2_2") (pintype "passive"))
      (node (ref "D1") (pin "2") (pinfunction "2_2") (pintype "power_in"))
      (node (ref "D2") (pin "1") (pinfunction "K2_1") (pintype "passive"))
      (node (ref "D3") (pin "1") (pinfunction "K2_1") (pintype "passive"))
      (node (ref "D4") (pin "1") (pinfunction "K2_1") (pintype "passive"))
      (node (ref "D9") (pin "1") (pinfunction "K2_1") (pintype "passive"))
      (node (ref "J1") (pin "4") (pinfunction "4_4") (pintype "passive"))
      (node (ref "J1") (pin "5") (pinfunction "5_5") (pintype "passive"))
      (node (ref "J2") (pin "11") (pinfunction "11_11") (pintype "passive"))
      (node (ref "J3") (pin "2") (pinfunction "2_2") (pintype "passive"))
      (node (ref "J3") (pin "4") (pinfunction "4_4") (pintype "passive"))
      (node (ref "J4") (pin "4") (pinfunction "4_4") (pintype "passive"))
      (node (ref "J4") (pin "6") (pinfunction "6_6") (pintype "passive"))
      (node (ref "J5") (pin "4") (pinfunction "4_4") (pintype "passive"))
      (node (ref "J5") (pin "6") (pinfunction "6_6") (pintype "passive"))
      (node (ref "J5") (pin "8") (pinfunction "8_8") (pintype "passive"))
      (node (ref "J8") (pin "6") (pinfunction "6_6") (pintype "passive"))
      (node (ref "J9") (pin "2") (pinfunction "2_2") (pintype "passive"))
      (node (ref "R15") (pin "1") (pinfunction "1_1") (pintype "passive"))
      (node (ref "R16") (pin "1") (pinfunction "1_1") (pintype "passive"))
      (node (ref "R17") (pin "1") (pinfunction "1_1") (pintype "passive"))
      (node (ref "R18") (pin "1") (pinfunction "1_1") (pintype "passive"))
      (node (ref "R2") (pin "1") (pinfunction "1_1") (pintype "passive"))
      (node (ref "R6") (pin "1") (pinfunction "1_1") (pintype "passive"))
      (node (ref "U1") (pin "12") (pinfunction "VSSA_12") (pintype "power_in"))
      (node (ref "U1") (pin "18") (pinfunction "VSS_18") (pintype "power_in"))
      (node (ref "U1") (pin "60") (pinfunction "BOOT0_60") (pintype "input"))
      (node (ref "U1") (pin "63") (pinfunction "VSS_63") (pintype "power_in"))
      (node (ref "U2") (pin "1") (pinfunction "~{EN}_1") (pintype "passive"))
      (node (ref "U2") (pin "12") (pinfunction "FON_12") (pintype "input"))
      (node (ref "U2") (pin "14") (pinfunction "GND_14") (pintype "passive"))
      (node (ref "U3") (pin "14") (pinfunction "RES_14") (pintype "passive"))
      (node (ref "U3") (pin "15") (pinfunction "RES_15") (pintype "passive"))
      (node (ref "U3") (pin "16") (pinfunction "RES_16") (pintype "passive"))
      (node (ref "U3") (pin "17") (pinfunction "RES_17") (pintype "passive"))
      (node (ref "U3") (pin "18") (pinfunction "RES_18") (pintype "passive"))
      (node (ref "U3") (pin "19") (pinfunction "GND_19") (pintype "power_in"))
      (node (ref "U3") (pin "20") (pinfunction "GND_20") (pintype "power_in"))
      (node (ref "U4") (pin "13") (pinfunction "MODE_13") (pintype "input"))
      (node (ref "U4") (pin "14") (pinfunction "F_14") (pintype "input"))
      (node (ref "U4") (pin "8") (pinfunction "VSS_8") (pintype "power_in"))
      (node (ref "U5") (pin "2") (pinfunction "PS_2") (pintype "passive"))
      (node (ref "U5") (pin "3") (pinfunction "GND_3") (pintype "passive"))
      (node (ref "U6") (pin "4") (pinfunction "GND_4") (pintype "power_in"))
    )
    (net (code "58") (name "MAINBAT") (class "Default")
      (node (ref "J2") (pin "12") (pinfunction "12_12") (pintype "passive"))
      (node (ref "R1") (pin "2") (pinfunction "2_2") (pintype "passive"))
    )
    (net (code "59") (name "Net-(D2-A2)") (class "Default")
      (node (ref "D2") (pin "2") (pinfunction "A2_2") (pintype "passive"))
      (node (ref "R3") (pin "1") (pinfunction "1_1") (pintype "passive"))
    )
    (net (code "60") (name "Net-(D3-A2)") (class "Default")
      (node (ref "D3") (pin "2") (pinfunction "A2_2") (pintype "passive"))
      (node (ref "R4") (pin "1") (pinfunction "1_1") (pintype "passive"))
    )
    (net (code "61") (name "Net-(D4-A2)") (class "Default")
      (node (ref "D4") (pin "2") (pinfunction "A2_2") (pintype "passive"))
      (node (ref "R5") (pin "1") (pinfunction "1_1") (pintype "passive"))
    )
    (net (code "62") (name "Net-(D9-A2)") (class "Default")
      (node (ref "D9") (pin "2") (pinfunction "A2_2") (pintype "passive"))
      (node (ref "R10") (pin "2") (pinfunction "2_2") (pintype "passive"))
    )
    (net (code "63") (name "Net-(F1-Pad2)") (class "Default")
      (node (ref "F1") (pin "2") (pinfunction "2_2") (pintype "passive"))
      (node (ref "J2") (pin "9") (pinfunction "9_9") (pintype "passive"))
    )
    (net (code "64") (name "Net-(F2-Pad2)") (class "Default")
      (node (ref "F2") (pin "2") (pinfunction "2_2") (pintype "passive"))
      (node (ref "J3") (pin "1") (pinfunction "1_1") (pintype "passive"))
      (node (ref "J3") (pin "3") (pinfunction "3_3") (pintype "passive"))
    )
    (net (code "65") (name "Net-(U1B-PC0)") (class "Default")
      (node (ref "R1") (pin "1") (pinfunction "1_1") (pintype "passive"))
      (node (ref "R2") (pin "2") (pinfunction "2_2") (pintype "passive"))
      (node (ref "U1") (pin "8") (pinfunction "PC0_8") (pintype "bidirectional"))
    )
    (net (code "66") (name "Net-(U1B-PH0{slash}OSC_IN)") (class "Default")
      (node (ref "C8") (pin "1") (pinfunction "1_1") (pintype "passive"))
      (node (ref "U1") (pin "5") (pinfunction "PH0/OSC_IN_5") (pintype "bidirectional"))
      (node (ref "Y1") (pin "2") (pinfunction "2_2") (pintype "power_in"))
    )
    (net (code "67") (name "Net-(U1B-PH1{slash}OSC_OUT)") (class "Default")
      (node (ref "C9") (pin "1") (pinfunction "1_1") (pintype "passive"))
      (node (ref "U1") (pin "6") (pinfunction "PH1/OSC_OUT_6") (pintype "bidirectional"))
      (node (ref "Y1") (pin "1") (pinfunction "1_1") (pintype "power_in"))
    )
    (net (code "68") (name "Net-(U1B-VCAP_1)") (class "Default")
      (node (ref "C10") (pin "2") (pinfunction "2_2") (pintype "passive"))
      (node (ref "U1") (pin "31") (pinfunction "VCAP_1_31") (pintype "power_in"))
    )
    (net (code "69") (name "Net-(U1B-VCAP_2)") (class "Default")
      (node (ref "C11") (pin "2") (pinfunction "2_2") (pintype "passive"))
      (node (ref "U1") (pin "47") (pinfunction "VCAP_2_47") (pintype "power_in"))
    )
    (net (code "70") (name "Net-(U2-C1+)") (class "Default")
      (node (ref "C12") (pin "2") (pinfunction "2_2") (pintype "passive"))
      (node (ref "U2") (pin "2") (pinfunction "C1+_2") (pintype "passive"))
    )
    (net (code "71") (name "Net-(U2-C1-)") (class "Default")
      (node (ref "C12") (pin "1") (pinfunction "1_1") (pintype "passive"))
      (node (ref "U2") (pin "4") (pinfunction "C1-_4") (pintype "passive"))
    )
    (net (code "72") (name "Net-(U2-C2+)") (class "Default")
      (node (ref "C14") (pin "2") (pinfunction "2_2") (pintype "passive"))
      (node (ref "U2") (pin "5") (pinfunction "C2+_5") (pintype "passive"))
    )
    (net (code "73") (name "Net-(U2-C2-)") (class "Default")
      (node (ref "C14") (pin "1") (pinfunction "1_1") (pintype "passive"))
      (node (ref "U2") (pin "6") (pinfunction "C2-_6") (pintype "passive"))
    )
    (net (code "74") (name "Net-(U2-V+)") (class "Default")
      (node (ref "C15") (pin "2") (pinfunction "2_2") (pintype "passive"))
      (node (ref "U2") (pin "3") (pinfunction "V+_3") (pintype "output"))
    )
    (net (code "75") (name "Net-(U2-V-)") (class "Default")
      (node (ref "C16") (pin "2") (pinfunction "2_2") (pintype "passive"))
      (node (ref "U2") (pin "7") (pinfunction "V-_7") (pintype "output"))
    )
    (net (code "76") (name "Net-(U2-~{INV})") (class "Default")
      (node (ref "R10") (pin "1") (pinfunction "1_1") (pintype "passive"))
      (node (ref "U2") (pin "10") (pinfunction "~{INV}_10") (pintype "output"))
    )
    (net (code "77") (name "Net-(U3-C1)") (class "Default")
      (node (ref "C18") (pin "2") (pinfunction "2_2") (pintype "passive"))
      (node (ref "U3") (pin "24") (pinfunction "C1_24") (pintype "passive"))
    )
    (net (code "78") (name "Net-(U3-CAP)") (class "Default")
      (node (ref "C19") (pin "2") (pinfunction "2_2") (pintype "passive"))
      (node (ref "U3") (pin "21") (pinfunction "CAP_21") (pintype "passive"))
    )
    (net (code "79") (name "Net-(U6-~{HOLD{slash}RESET!(IO3)})") (class "Default")
      (node (ref "R19") (pin "1") (pinfunction "1_1") (pintype "passive"))
      (node (ref "U6") (pin "7") (pinfunction "~{HOLD/RESET!(IO3)}_7") (pintype "bidirectional"))
    )
    (net (code "80") (name "unconnected-(J2-Pad7)") (class "Default")
      (node (ref "J2") (pin "7") (pinfunction "7_7") (pintype "passive"))
    )
    (net (code "81") (name "unconnected-(J2-Pad10)") (class "Default")
      (node (ref "J2") (pin "10") (pinfunction "10_10") (pintype "passive"))
    )
    (net (code "82") (name "unconnected-(J7-Pad3)") (class "Default")
      (node (ref "J7") (pin "3") (pinfunction "3_3") (pintype "passive"))
    )
    (net (code "83") (name "unconnected-(J7-Pad4)") (class "Default")
      (node (ref "J7") (pin "4") (pinfunction "4_4") (pintype "passive"))
    )
    (net (code "84") (name "unconnected-(J7-Pad5)") (class "Default")
      (node (ref "J7") (pin "5") (pinfunction "5_5") (pintype "passive"))
    )
    (net (code "85") (name "unconnected-(J7-Pad6)") (class "Default")
      (node (ref "J7") (pin "6") (pinfunction "6_6") (pintype "passive"))
    )
    (net (code "86") (name "unconnected-(J8-Pad1)") (class "Default")
      (node (ref "J8") (pin "1") (pinfunction "1_1") (pintype "passive"))
    )
    (net (code "87") (name "unconnected-(J8-Pad2)") (class "Default")
      (node (ref "J8") (pin "2") (pinfunction "2_2") (pintype "passive"))
    )
    (net (code "88") (name "unconnected-(J8-Pad3)") (class "Default")
      (node (ref "J8") (pin "3") (pinfunction "3_3") (pintype "passive"))
    )
    (net (code "89") (name "unconnected-(J8-Pad4)") (class "Default")
      (node (ref "J8") (pin "4") (pinfunction "4_4") (pintype "passive"))
    )
    (net (code "90") (name "unconnected-(U1B-PA15-Pad50)") (class "Default")
      (node (ref "U1") (pin "50") (pinfunction "PA15_50") (pintype "bidirectional"))
    )
    (net (code "91") (name "unconnected-(U1B-PB6-Pad58)") (class "Default")
      (node (ref "U1") (pin "58") (pinfunction "PB6_58") (pintype "bidirectional"))
    )
    (net (code "92") (name "unconnected-(U1B-PB7-Pad59)") (class "Default")
      (node (ref "U1") (pin "59") (pinfunction "PB7_59") (pintype "bidirectional"))
    )
    (net (code "93") (name "unconnected-(U1B-PB8-Pad61)") (class "Default")
      (node (ref "U1") (pin "61") (pinfunction "PB8_61") (pintype "bidirectional"))
    )
    (net (code "94") (name "unconnected-(U1B-PB9-Pad62)") (class "Default")
      (node (ref "U1") (pin "62") (pinfunction "PB9_62") (pintype "bidirectional"))
    )
    (net (code "95") (name "unconnected-(U1B-PB12-Pad33)") (class "Default")
      (node (ref "U1") (pin "33") (pinfunction "PB12_33") (pintype "bidirectional"))
    )
    (net (code "96") (name "unconnected-(U1B-PC1-Pad9)") (class "Default")
      (node (ref "U1") (pin "9") (pinfunction "PC1_9") (pintype "bidirectional"))
    )
    (net (code "97") (name "unconnected-(U1B-PC9-Pad40)") (class "Default")
      (node (ref "U1") (pin "40") (pinfunction "PC9_40") (pintype "bidirectional"))
    )
    (net (code "98") (name "unconnected-(U1B-PC13-Pad2)") (class "Default")
      (node (ref "U1") (pin "2") (pinfunction "PC13_2") (pintype "bidirectional"))
    )
    (net (code "99") (name "unconnected-(U3-DEN_A{slash}G-Pad13)") (class "Default")
      (node (ref "U3") (pin "13") (pinfunction "DEN_A/G_13") (pintype "passive+no_connect"))
    )
    (net (code "100") (name "unconnected-(U3-DRDY_M-Pad9)") (class "Default")
      (node (ref "U3") (pin "9") (pinfunction "DRDY_M_9") (pintype "passive+no_connect"))
    )
    (net (code "101") (name "unconnected-(U3-INT1_A{slash}G-Pad11)") (class "Default")
      (node (ref "U3") (pin "11") (pinfunction "INT1_A/G_11") (pintype "passive+no_connect"))
    )
    (net (code "102") (name "unconnected-(U3-INT2_A{slash}G-Pad12)") (class "Default")
      (node (ref "U3") (pin "12") (pinfunction "INT2_A/G_12") (pintype "passive+no_connect"))
    )
    (net (code "103") (name "unconnected-(U3-INT_M-Pad10)") (class "Default")
      (node (ref "U3") (pin "10") (pinfunction "INT_M_10") (pintype "passive+no_connect"))
    )
    (net (code "104") (name "unconnected-(U4-L-Pad15)") (class "Default")
      (node (ref "U4") (pin "15") (pinfunction "L_15") (pintype "output+no_connect"))
    )
  )
)
